# touch-board-ks-edition.net
KiCad netlist of a schematic drawn in EAGLE
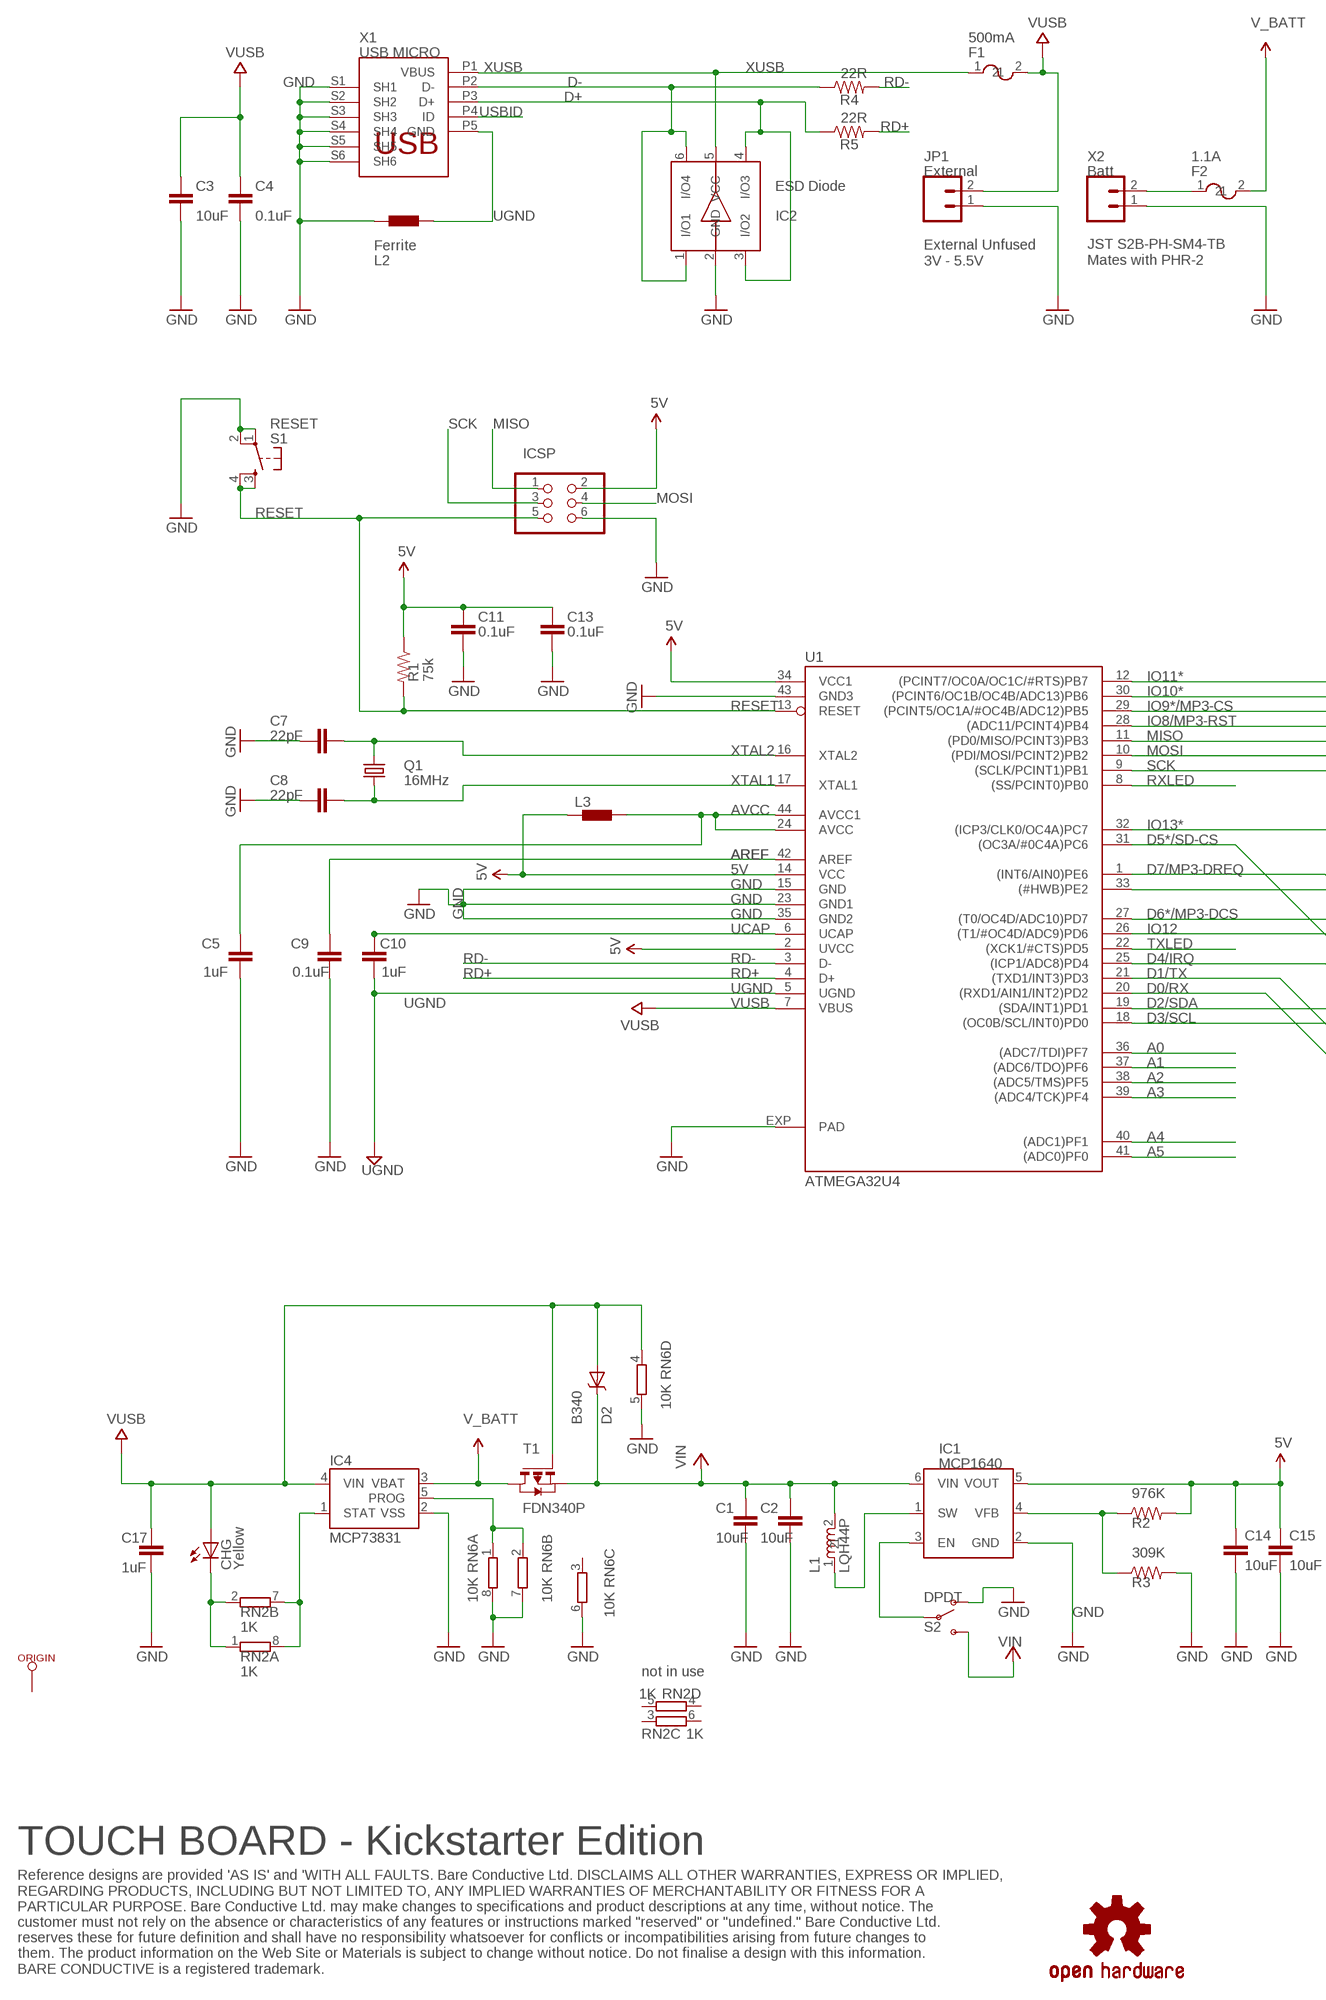
[diagram p0: schematic, sheet 1, part 1 of 2]
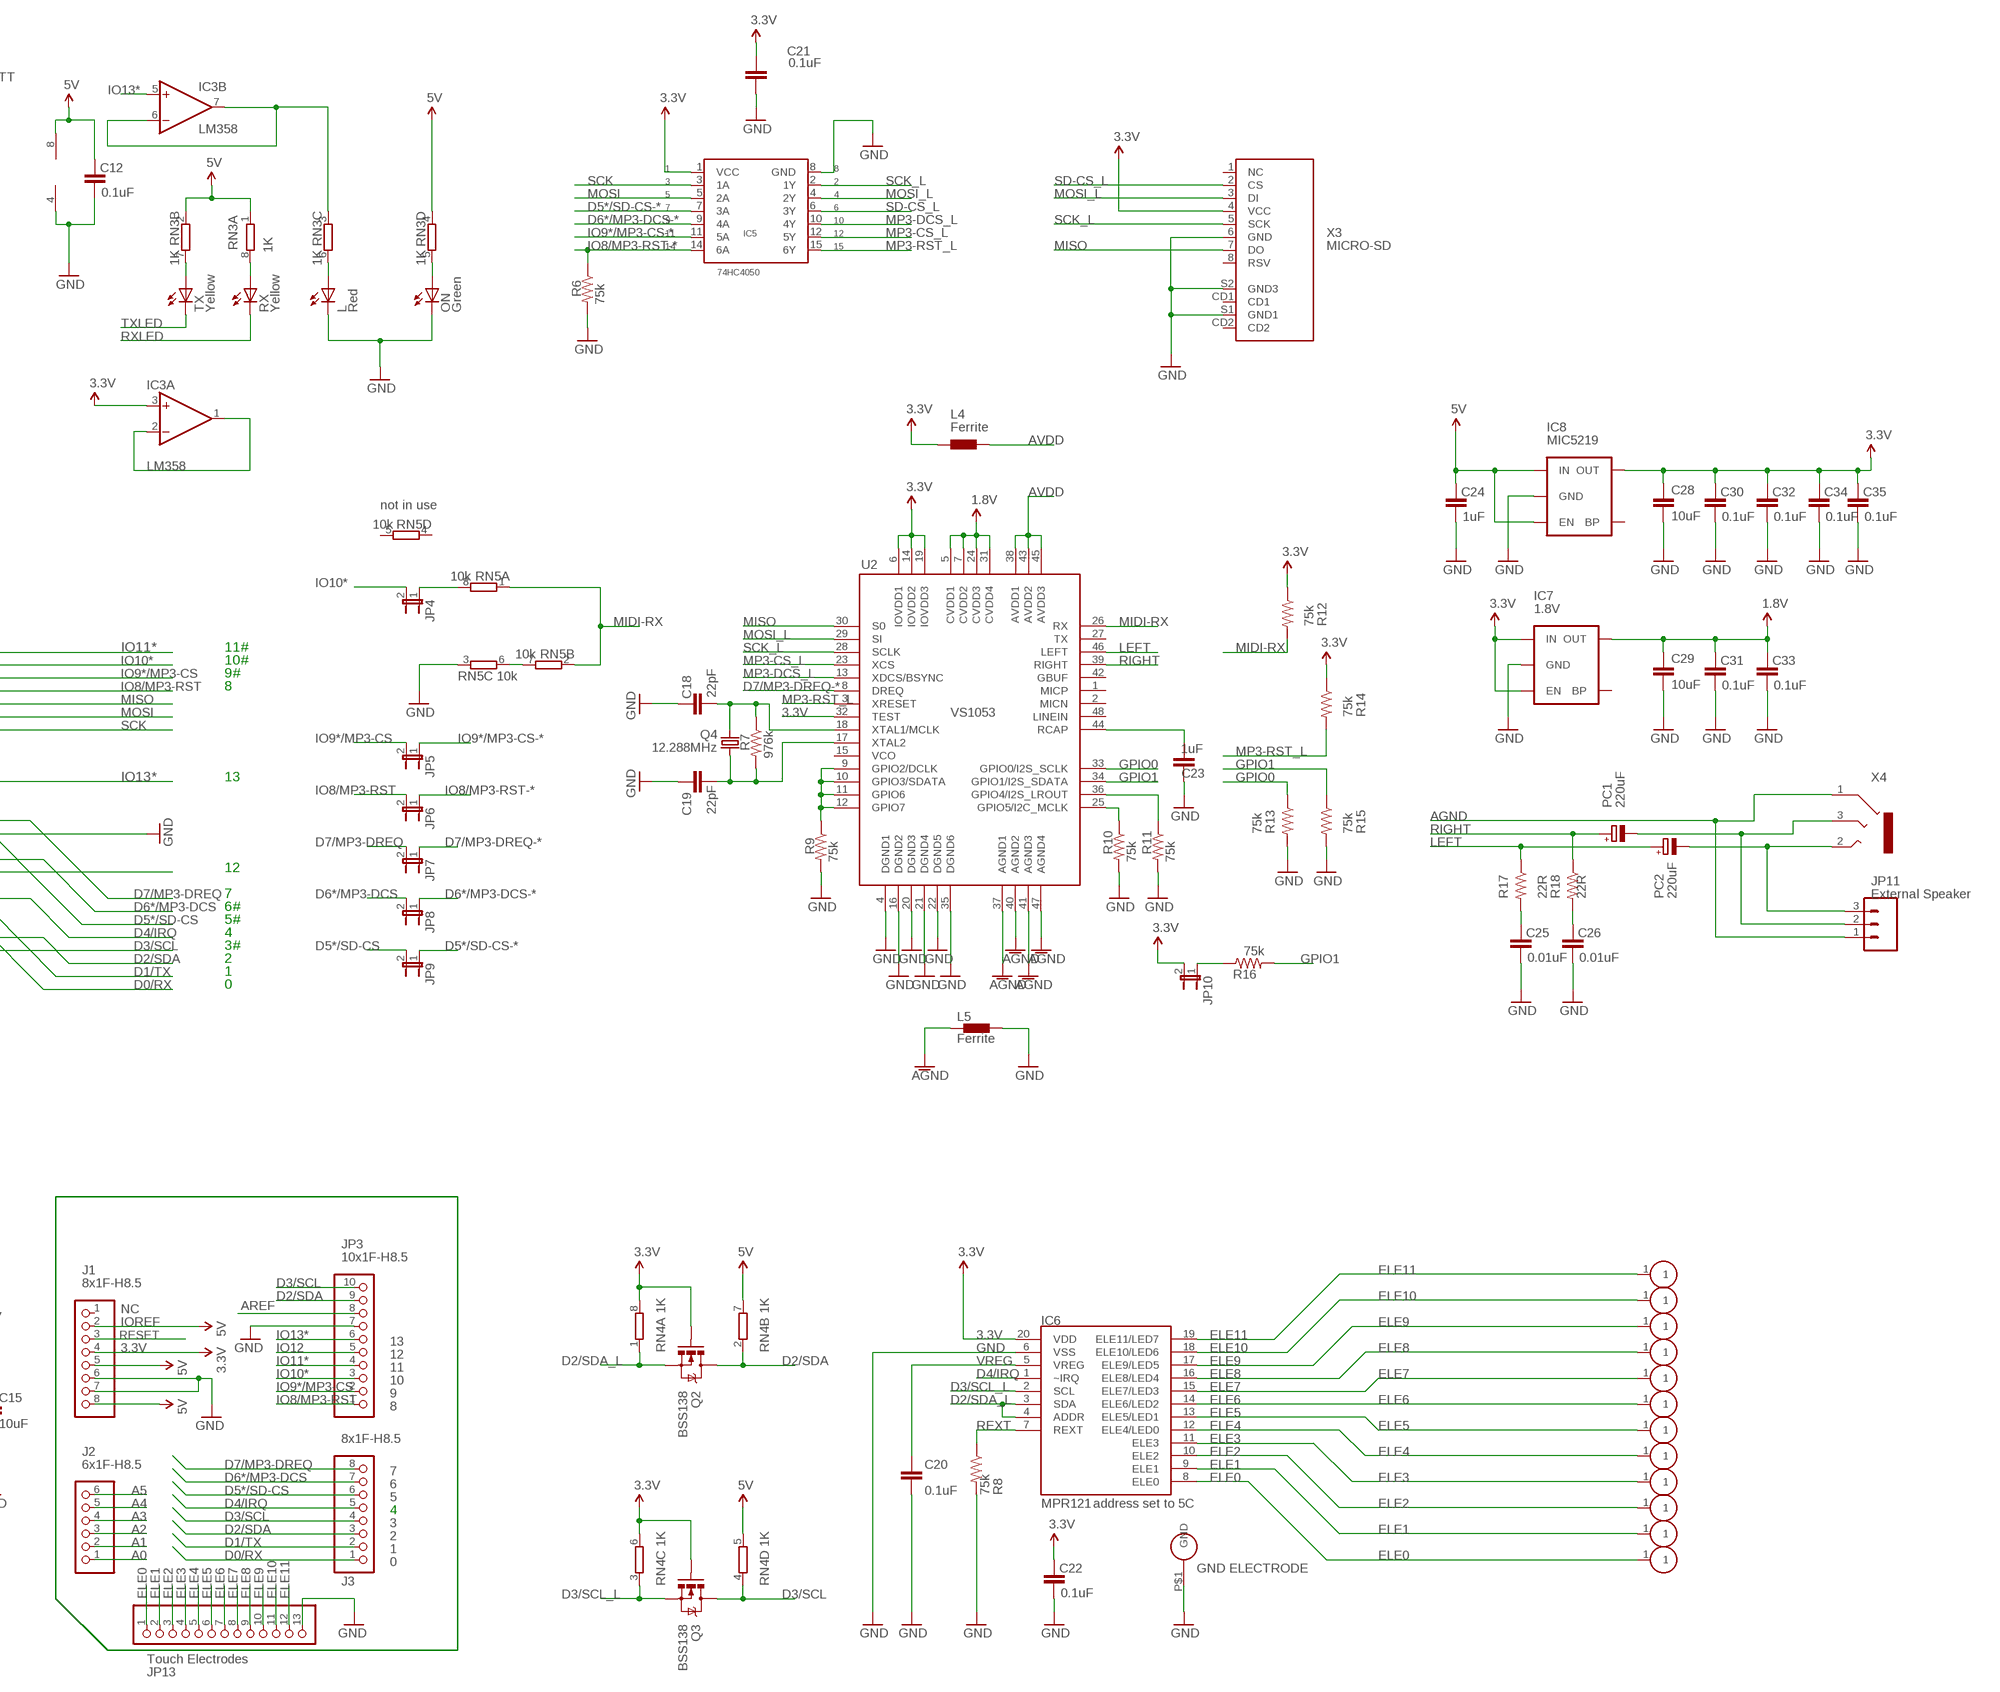
[diagram p1: schematic, sheet 1, part 2 of 2]

(export (version "E")
  (design (tool "Eeschema 10.0.6"))
  (components
    (comp (ref "C1")
      (value "10uF")
      (footprint "eagle-import:1206")
      (libsource (lib "eagle-import") (part "SparkFun-Capacitors_CAP1206"))
    )
    (comp (ref "C2")
      (value "10uF")
      (footprint "eagle-import:1206")
      (libsource (lib "eagle-import") (part "SparkFun-Capacitors_CAP1206"))
    )
    (comp (ref "C3")
      (value "10uF")
      (footprint "eagle-import:1206")
      (libsource (lib "eagle-import") (part "SparkFun-Capacitors_CAP1206"))
    )
    (comp (ref "C4")
      (value "0.1uF")
      (footprint "eagle-import:0402-CAP")
      (libsource (lib "eagle-import") (part "CAP0402-CAP"))
    )
    (comp (ref "C5")
      (value "1uF")
      (footprint "eagle-import:0402-CAP")
      (libsource (lib "eagle-import") (part "CAP0402-CAP"))
    )
    (comp (ref "C7")
      (value "22pF")
      (footprint "eagle-import:0402-CAP")
      (libsource (lib "eagle-import") (part "CAP0402-CAP"))
    )
    (comp (ref "C8")
      (value "22pF")
      (footprint "eagle-import:0402-CAP")
      (libsource (lib "eagle-import") (part "CAP0402-CAP"))
    )
    (comp (ref "C9")
      (value "0.1uF")
      (footprint "eagle-import:0402-CAP")
      (libsource (lib "eagle-import") (part "CAP0402-CAP"))
    )
    (comp (ref "C10")
      (value "1uF")
      (footprint "eagle-import:0402-CAP")
      (libsource (lib "eagle-import") (part "CAP0402-CAP"))
    )
    (comp (ref "C11")
      (value "0.1uF")
      (footprint "eagle-import:0402-CAP")
      (libsource (lib "eagle-import") (part "CAP0402-CAP"))
    )
    (comp (ref "C12")
      (value "0.1uF")
      (footprint "eagle-import:0402-CAP")
      (libsource (lib "eagle-import") (part "CAP0402-CAP"))
    )
    (comp (ref "C13")
      (value "0.1uF")
      (footprint "eagle-import:0402-CAP")
      (libsource (lib "eagle-import") (part "CAP0402-CAP"))
    )
    (comp (ref "C14")
      (value "10uF")
      (footprint "eagle-import:1206")
      (libsource (lib "eagle-import") (part "SparkFun-Capacitors_CAP1206"))
    )
    (comp (ref "C15")
      (value "10uF")
      (footprint "eagle-import:1206")
      (libsource (lib "eagle-import") (part "SparkFun-Capacitors_CAP1206"))
    )
    (comp (ref "C17")
      (value "1uF")
      (footprint "eagle-import:0402-CAP")
      (libsource (lib "eagle-import") (part "CAP0402-CAP"))
    )
    (comp (ref "C18")
      (value "22pF")
      (footprint "eagle-import:0402-CAP")
      (libsource (lib "eagle-import") (part "CAP0402-CAP"))
    )
    (comp (ref "C19")
      (value "22pF")
      (footprint "eagle-import:0402-CAP")
      (libsource (lib "eagle-import") (part "CAP0402-CAP"))
    )
    (comp (ref "C20")
      (value "0.1uF")
      (footprint "eagle-import:0402-CAP")
      (libsource (lib "eagle-import") (part "CAP0402-CAP"))
    )
    (comp (ref "C21")
      (value "0.1uF")
      (footprint "eagle-import:0402-CAP")
      (libsource (lib "eagle-import") (part "CAP0402-CAP"))
    )
    (comp (ref "C22")
      (value "0.1uF")
      (footprint "eagle-import:0402-CAP")
      (libsource (lib "eagle-import") (part "CAP0402-CAP"))
    )
    (comp (ref "C23")
      (value "1uF")
      (footprint "eagle-import:0402-CAP")
      (libsource (lib "eagle-import") (part "CAP0402-CAP"))
    )
    (comp (ref "C24")
      (value "1uF")
      (footprint "eagle-import:0402-CAP")
      (libsource (lib "eagle-import") (part "CAP0402-CAP"))
    )
    (comp (ref "C25")
      (value "0.01uF")
      (footprint "eagle-import:0402-CAP")
      (libsource (lib "eagle-import") (part "CAP0402-CAP"))
    )
    (comp (ref "C26")
      (value "0.01uF")
      (footprint "eagle-import:0402-CAP")
      (libsource (lib "eagle-import") (part "CAP0402-CAP"))
    )
    (comp (ref "C28")
      (value "10uF")
      (footprint "eagle-import:1206")
      (libsource (lib "eagle-import") (part "SparkFun-Capacitors_CAP1206"))
    )
    (comp (ref "C29")
      (value "10uF")
      (footprint "eagle-import:1206")
      (libsource (lib "eagle-import") (part "SparkFun-Capacitors_CAP1206"))
    )
    (comp (ref "C30")
      (value "0.1uF")
      (footprint "eagle-import:0402-CAP")
      (libsource (lib "eagle-import") (part "CAP0402-CAP"))
    )
    (comp (ref "C31")
      (value "0.1uF")
      (footprint "eagle-import:0402-CAP")
      (libsource (lib "eagle-import") (part "CAP0402-CAP"))
    )
    (comp (ref "C32")
      (value "0.1uF")
      (footprint "eagle-import:0402-CAP")
      (libsource (lib "eagle-import") (part "CAP0402-CAP"))
    )
    (comp (ref "C33")
      (value "0.1uF")
      (footprint "eagle-import:0402-CAP")
      (libsource (lib "eagle-import") (part "CAP0402-CAP"))
    )
    (comp (ref "C34")
      (value "0.1uF")
      (footprint "eagle-import:0402-CAP")
      (libsource (lib "eagle-import") (part "CAP0402-CAP"))
    )
    (comp (ref "C35")
      (value "0.1uF")
      (footprint "eagle-import:0402-CAP")
      (libsource (lib "eagle-import") (part "CAP0402-CAP"))
    )
    (comp (ref "CHG")
      (value "Yellow")
      (footprint "eagle-import:CHIPLED_0805")
      (libsource (lib "eagle-import") (part "LEDCHIPLED_0805"))
    )
    (comp (ref "D2")
      (value "B340")
      (footprint "eagle-import:SMA-DIODE")
      (libsource (lib "eagle-import") (part "DIODE-SCHOTTKY_"))
    )
    (comp (ref "F1")
      (value "500mA")
      (footprint "eagle-import:0805")
      (libsource (lib "eagle-import") (part "PTC"))
    )
    (comp (ref "F2")
      (value "1.1A")
      (footprint "eagle-import:0805")
      (libsource (lib "eagle-import") (part "PTC"))
    )
    (comp (ref "IC1")
      (value "MCP1640")
      (footprint "eagle-import:6-LEAD-SOT23")
      (libsource (lib "eagle-import") (part "BOOST-REG"))
    )
    (comp (ref "IC2")
      (value "ESD Diode")
      (footprint "eagle-import:SOT457")
      (libsource (lib "eagle-import") (part "PRTR5V"))
    )
    (comp (ref "IC3")
      (value "LM358")
      (footprint "eagle-import:MSOP08")
      (libsource (lib "eagle-import") (part "LMV358?MMX"))
    )
    (comp (ref "IC4")
      (value "MCP73831")
      (footprint "eagle-import:SOT23-5")
      (libsource (lib "eagle-import") (part "MCP73831"))
    )
    (comp (ref "IC5")
      (value "74HC4050")
      (footprint "eagle-import:TSSOP-16")
      (libsource (lib "eagle-import") (part "74HC4050PW"))
    )
    (comp (ref "IC6")
      (value "MPR121")
      (footprint "eagle-import:QFN-20-0.4MM")
      (libsource (lib "eagle-import") (part "MPR121QFN20"))
    )
    (comp (ref "IC7")
      (value "1.8V")
      (footprint "eagle-import:SC70")
      (libsource (lib "eagle-import") (part "V_REG_LDOSMD2"))
    )
    (comp (ref "IC8")
      (value "MIC5219")
      (footprint "eagle-import:SOT23-5")
      (libsource (lib "eagle-import") (part "V_REG_LDOSMD"))
    )
    (comp (ref "ICSP")
      (value "ICSP")
      (footprint "eagle-import:2X03")
      (libsource (lib "eagle-import") (part "PINHD-2X3"))
    )
    (comp (ref "J1")
      (value "8x1F-H8.5")
      (footprint "eagle-import:1X08")
      (libsource (lib "eagle-import") (part "PINHD-1X8"))
    )
    (comp (ref "J2")
      (value "6x1F-H8.5")
      (footprint "eagle-import:1X06")
      (libsource (lib "eagle-import") (part "PINHD-1X6"))
    )
    (comp (ref "J3")
      (value "8x1F-H8.5")
      (footprint "eagle-import:1X08")
      (libsource (lib "eagle-import") (part "PINHD-1X8"))
    )
    (comp (ref "JP1")
      (value "External")
      (footprint "eagle-import:1X02")
      (libsource (lib "eagle-import") (part "M02PTH"))
    )
    (comp (ref "JP3")
      (value "10x1F-H8.5")
      (footprint "eagle-import:1X10")
      (libsource (lib "eagle-import") (part "PINHD-1X10"))
    )
    (comp (ref "JP4")
      (value "JUMPER-2SMD-NO")
      (footprint "eagle-import:SJ_2S-NO")
      (libsource (lib "eagle-import") (part "JUMPER-2SMD-NO"))
    )
    (comp (ref "JP5")
      (value "JUMPER-2SMD-NC")
      (footprint "eagle-import:SJ_2S")
      (libsource (lib "eagle-import") (part "JUMPER-2SMD-NC"))
    )
    (comp (ref "JP6")
      (value "JUMPER-2SMD-NC")
      (footprint "eagle-import:SJ_2S")
      (libsource (lib "eagle-import") (part "JUMPER-2SMD-NC"))
    )
    (comp (ref "JP7")
      (value "JUMPER-2SMD-NC")
      (footprint "eagle-import:SJ_2S")
      (libsource (lib "eagle-import") (part "JUMPER-2SMD-NC"))
    )
    (comp (ref "JP8")
      (value "JUMPER-2SMD-NC")
      (footprint "eagle-import:SJ_2S")
      (libsource (lib "eagle-import") (part "JUMPER-2SMD-NC"))
    )
    (comp (ref "JP9")
      (value "JUMPER-2SMD-NC")
      (footprint "eagle-import:SJ_2S")
      (libsource (lib "eagle-import") (part "JUMPER-2SMD-NC"))
    )
    (comp (ref "JP10")
      (value "JUMPER-2SMD-NO")
      (footprint "eagle-import:SJ_2S-NO")
      (libsource (lib "eagle-import") (part "JUMPER-2SMD-NO"))
    )
    (comp (ref "JP11")
      (value "External Speaker")
      (footprint "eagle-import:1X03")
      (libsource (lib "eagle-import") (part "M03PTH"))
    )
    (comp (ref "JP13")
      (value "Touch Electrodes")
      (footprint "eagle-import:1X13")
      (libsource (lib "eagle-import") (part "PINHD-1X13"))
    )
    (comp (ref "L")
      (value "Red")
      (footprint "eagle-import:CHIPLED_0805")
      (libsource (lib "eagle-import") (part "LEDCHIPLED_0805"))
    )
    (comp (ref "L1")
      (value "LQH44P")
      (footprint "eagle-import:LQH44PN100MP0L")
      (libsource (lib "eagle-import") (part "LQH44P"))
    )
    (comp (ref "L2")
      (value "Ferrite")
      (footprint "eagle-import:0402")
      (libsource (lib "eagle-import") (part "BLM15HB121SN1"))
    )
    (comp (ref "L3")
      (value "BLM15HB121SN1")
      (footprint "eagle-import:0402")
      (libsource (lib "eagle-import") (part "BLM15HB121SN1"))
    )
    (comp (ref "L4")
      (value "Ferrite")
      (footprint "eagle-import:0402")
      (libsource (lib "eagle-import") (part "BLM15HB121SN1"))
    )
    (comp (ref "L5")
      (value "Ferrite")
      (footprint "eagle-import:0402")
      (libsource (lib "eagle-import") (part "BLM15HB121SN1"))
    )
    (comp (ref "ON")
      (value "Green")
      (footprint "eagle-import:CHIPLED_0805")
      (libsource (lib "eagle-import") (part "LEDCHIPLED_0805"))
    )
    (comp (ref "ORIGIN")
      (value "TP_SP")
      (footprint "eagle-import:TP-SP")
      (libsource (lib "eagle-import") (part "TP_SP"))
    )
    (comp (ref "PC1")
      (value "220uF")
      (footprint "eagle-import:PANASONIC_D")
      (libsource (lib "eagle-import") (part "CPOL-EUD"))
    )
    (comp (ref "PC2")
      (value "220uF")
      (footprint "eagle-import:PANASONIC_D")
      (libsource (lib "eagle-import") (part "CPOL-EUD"))
    )
    (comp (ref "Q1")
      (value "16MHz")
      (footprint "eagle-import:CRYSTAL-SMD-5X3")
      (libsource (lib "eagle-import") (part "CRYSTAL5X3"))
    )
    (comp (ref "Q2")
      (value "BSS138")
      (footprint "eagle-import:SOT23-3")
      (libsource (lib "eagle-import") (part "MOSFET-NCHANNELSMD"))
    )
    (comp (ref "Q3")
      (value "BSS138")
      (footprint "eagle-import:SOT23-3")
      (libsource (lib "eagle-import") (part "MOSFET-NCHANNELSMD"))
    )
    (comp (ref "Q4")
      (value "12.288MHz")
      (footprint "eagle-import:CRYSTAL-SMD-5X3")
      (libsource (lib "eagle-import") (part "CRYSTAL5X3"))
    )
    (comp (ref "R1")
      (value "75k")
      (footprint "eagle-import:0402-RES")
      (libsource (lib "eagle-import") (part "RESISTOR0402-RES"))
    )
    (comp (ref "R2")
      (value "976K")
      (footprint "eagle-import:0402-RES")
      (libsource (lib "eagle-import") (part "RESISTOR0402-RES"))
    )
    (comp (ref "R3")
      (value "309K")
      (footprint "eagle-import:0402-RES")
      (libsource (lib "eagle-import") (part "RESISTOR0402-RES"))
    )
    (comp (ref "R4")
      (value "22R")
      (footprint "eagle-import:0402-RES")
      (libsource (lib "eagle-import") (part "RESISTOR0402-RES"))
    )
    (comp (ref "R5")
      (value "22R")
      (footprint "eagle-import:0402-RES")
      (libsource (lib "eagle-import") (part "RESISTOR0402-RES"))
    )
    (comp (ref "R6")
      (value "75k")
      (footprint "eagle-import:0402-RES")
      (libsource (lib "eagle-import") (part "RESISTOR0402-RES"))
    )
    (comp (ref "R7")
      (value "976k")
      (footprint "eagle-import:0402-RES")
      (libsource (lib "eagle-import") (part "RESISTOR0402-RES"))
    )
    (comp (ref "R8")
      (value "75k")
      (footprint "eagle-import:0402-RES")
      (libsource (lib "eagle-import") (part "RESISTOR0402-RES"))
    )
    (comp (ref "R9")
      (value "75k")
      (footprint "eagle-import:0402-RES")
      (libsource (lib "eagle-import") (part "RESISTOR0402-RES"))
    )
    (comp (ref "R10")
      (value "75k")
      (footprint "eagle-import:0402-RES")
      (libsource (lib "eagle-import") (part "RESISTOR0402-RES"))
    )
    (comp (ref "R11")
      (value "75k")
      (footprint "eagle-import:0402-RES")
      (libsource (lib "eagle-import") (part "RESISTOR0402-RES"))
    )
    (comp (ref "R12")
      (value "75k")
      (footprint "eagle-import:0402-RES")
      (libsource (lib "eagle-import") (part "RESISTOR0402-RES"))
    )
    (comp (ref "R13")
      (value "75k")
      (footprint "eagle-import:0402-RES")
      (libsource (lib "eagle-import") (part "RESISTOR0402-RES"))
    )
    (comp (ref "R14")
      (value "75k")
      (footprint "eagle-import:0402-RES")
      (libsource (lib "eagle-import") (part "RESISTOR0402-RES"))
    )
    (comp (ref "R15")
      (value "75k")
      (footprint "eagle-import:0402-RES")
      (libsource (lib "eagle-import") (part "RESISTOR0402-RES"))
    )
    (comp (ref "R16")
      (value "75k")
      (footprint "eagle-import:0402-RES")
      (libsource (lib "eagle-import") (part "RESISTOR0402-RES"))
    )
    (comp (ref "R17")
      (value "22R")
      (footprint "eagle-import:0402-RES")
      (libsource (lib "eagle-import") (part "RESISTOR0402-RES"))
    )
    (comp (ref "R18")
      (value "22R")
      (footprint "eagle-import:0402-RES")
      (libsource (lib "eagle-import") (part "RESISTOR0402-RES"))
    )
    (comp (ref "RN2")
      (value "1K")
      (footprint "eagle-import:CAY16")
      (libsource (lib "eagle-import") (part "4R-NCAY16"))
    )
    (comp (ref "RN3")
      (value "1K")
      (footprint "eagle-import:CAY16")
      (libsource (lib "eagle-import") (part "4R-NCAY16"))
    )
    (comp (ref "RN4")
      (value "1K")
      (footprint "eagle-import:CAY16")
      (libsource (lib "eagle-import") (part "4R-NCAY16"))
    )
    (comp (ref "RN5")
      (value "10k")
      (footprint "eagle-import:CAY16")
      (libsource (lib "eagle-import") (part "4R-NCAY16"))
    )
    (comp (ref "RN6")
      (value "10K")
      (footprint "eagle-import:CAY16")
      (libsource (lib "eagle-import") (part "4R-NCAY16"))
    )
    (comp (ref "RX")
      (value "Yellow")
      (footprint "eagle-import:CHIPLED_0805")
      (libsource (lib "eagle-import") (part "LEDCHIPLED_0805"))
    )
    (comp (ref "S1")
      (value "RESET")
      (footprint "eagle-import:TACTILE_SWITCH_SMD@1")
      (libsource (lib "eagle-import") (part "TAC_SWITCHSND"))
    )
    (comp (ref "S2")
      (value "DPDT")
      (footprint "eagle-import:JS202011SCQN")
      (libsource (lib "eagle-import") (part "DPDT-SWITCH"))
    )
    (comp (ref "T1")
      (value "FDN340P")
      (footprint "eagle-import:SOT-23")
      (libsource (lib "eagle-import") (part "PMOSSOT23"))
    )
    (comp (ref "TX")
      (value "Yellow")
      (footprint "eagle-import:CHIPLED_0805")
      (libsource (lib "eagle-import") (part "LEDCHIPLED_0805"))
    )
    (comp (ref "U$1")
      (value "EDGE-ELEC-LEFT")
      (footprint "eagle-import:EDGE-ELEC-LEFT")
      (libsource (lib "eagle-import") (part "EDGE-ELEC-LEFT"))
    )
    (comp (ref "U$3")
      (value "EDGE-ELEC-RIGHT")
      (footprint "eagle-import:EDGE-ELEC-RIGHT")
      (libsource (lib "eagle-import") (part "EDGE-ELEC-RIGHT"))
    )
    (comp (ref "U$6")
      (value "EDGE-GND")
      (footprint "eagle-import:EDGE-GND")
      (libsource (lib "eagle-import") (part "EDGE-GND"))
    )
    (comp (ref "U$8")
      (value "OSHW-LOGO")
      (footprint "eagle-import:OSHW-LOGO")
      (libsource (lib "eagle-import") (part "OSHW-LOGO"))
    )
    (comp (ref "U$17")
      (value "EDGE-ELEC")
      (footprint "eagle-import:EDGE-ELEC")
      (libsource (lib "eagle-import") (part "EDGE-ELEC"))
    )
    (comp (ref "U$18")
      (value "EDGE-ELEC")
      (footprint "eagle-import:EDGE-ELEC")
      (libsource (lib "eagle-import") (part "EDGE-ELEC"))
    )
    (comp (ref "U$22")
      (value "EDGE-ELEC")
      (footprint "eagle-import:EDGE-ELEC")
      (libsource (lib "eagle-import") (part "EDGE-ELEC"))
    )
    (comp (ref "U$24")
      (value "EDGE-ELEC")
      (footprint "eagle-import:EDGE-ELEC")
      (libsource (lib "eagle-import") (part "EDGE-ELEC"))
    )
    (comp (ref "U$26")
      (value "EDGE-ELEC")
      (footprint "eagle-import:EDGE-ELEC")
      (libsource (lib "eagle-import") (part "EDGE-ELEC"))
    )
    (comp (ref "U$27")
      (value "EDGE-ELEC")
      (footprint "eagle-import:EDGE-ELEC")
      (libsource (lib "eagle-import") (part "EDGE-ELEC"))
    )
    (comp (ref "U$28")
      (value "EDGE-ELEC")
      (footprint "eagle-import:EDGE-ELEC")
      (libsource (lib "eagle-import") (part "EDGE-ELEC"))
    )
    (comp (ref "U$29")
      (value "EDGE-ELEC")
      (footprint "eagle-import:EDGE-ELEC")
      (libsource (lib "eagle-import") (part "EDGE-ELEC"))
    )
    (comp (ref "U$30")
      (value "EDGE-ELEC")
      (footprint "eagle-import:EDGE-ELEC")
      (libsource (lib "eagle-import") (part "EDGE-ELEC"))
    )
    (comp (ref "U$31")
      (value "EDGE-ELEC")
      (footprint "eagle-import:EDGE-ELEC")
      (libsource (lib "eagle-import") (part "EDGE-ELEC"))
    )
    (comp (ref "U1")
      (value "ATMEGA32U4")
      (footprint "eagle-import:QFN44ML7X7")
      (libsource (lib "eagle-import") (part "ATMEGA32U4-XUMU"))
    )
    (comp (ref "U2")
      (value "VS1053")
      (footprint "eagle-import:LQFP-48")
      (libsource (lib "eagle-import") (part "VS1033"))
    )
    (comp (ref "X1")
      (value "USB MICRO")
      (footprint "eagle-import:CON2_USB_MICRO_B_AT")
      (libsource (lib "eagle-import") (part "MYCON2_USB-MINI-B"))
    )
    (comp (ref "X2")
      (value "Batt")
      (footprint "eagle-import:JST-2-SMD")
      (libsource (lib "eagle-import") (part "M02-JST-2MM-SMT"))
    )
    (comp (ref "X3")
      (value "MICRO-SD")
      (footprint "eagle-import:MSDC-PP-02")
      (libsource (lib "eagle-import") (part "TOBY-SD"))
    )
    (comp (ref "X4")
      (value "SJ-3523")
      (footprint "eagle-import:3POLE-JACK")
      (libsource (lib "eagle-import") (part "SJ-3523"))
    )
  )
  (nets
    (net (code "1") (name "/A0") (class "Default")
      (node (ref "J2") (pin "1") (pinfunction "1_1") (pintype "passive"))
      (node (ref "U1") (pin "36") (pinfunction "(ADC7/TDI)PF7_36") (pintype "bidirectional"))
    )
    (net (code "2") (name "/A1") (class "Default")
      (node (ref "J2") (pin "2") (pinfunction "2_2") (pintype "passive"))
      (node (ref "U1") (pin "37") (pinfunction "(ADC6/TDO)PF6_37") (pintype "bidirectional"))
    )
    (net (code "3") (name "/A2") (class "Default")
      (node (ref "J2") (pin "3") (pinfunction "3_3") (pintype "passive"))
      (node (ref "U1") (pin "38") (pinfunction "(ADC5/TMS)PF5_38") (pintype "bidirectional"))
    )
    (net (code "4") (name "/A3") (class "Default")
      (node (ref "J2") (pin "4") (pinfunction "4_4") (pintype "passive"))
      (node (ref "U1") (pin "39") (pinfunction "(ADC4/TCK)PF4_39") (pintype "bidirectional"))
    )
    (net (code "5") (name "/A4") (class "Default")
      (node (ref "J2") (pin "5") (pinfunction "5_5") (pintype "passive"))
      (node (ref "U1") (pin "40") (pinfunction "(ADC1)PF1_40") (pintype "bidirectional"))
    )
    (net (code "6") (name "/A5") (class "Default")
      (node (ref "J2") (pin "6") (pinfunction "6_6") (pintype "passive"))
      (node (ref "U1") (pin "41") (pinfunction "(ADC0)PF0_41") (pintype "bidirectional"))
    )
    (net (code "7") (name "/AREF") (class "Default")
      (node (ref "C9") (pin "2") (pinfunction "2_2") (pintype "passive"))
      (node (ref "JP3") (pin "8") (pinfunction "8_8") (pintype "passive"))
      (node (ref "U1") (pin "42") (pinfunction "AREF_42") (pintype "power_in"))
    )
    (net (code "8") (name "/AVCC") (class "Default")
      (node (ref "C5") (pin "2") (pinfunction "2_2") (pintype "passive"))
      (node (ref "L3") (pin "2") (pinfunction "2_2") (pintype "passive"))
      (node (ref "U1") (pin "24") (pinfunction "AVCC_24") (pintype "power_in"))
      (node (ref "U1") (pin "44") (pinfunction "AVCC1_44") (pintype "power_in"))
    )
    (net (code "9") (name "/AVDD") (class "Default")
      (node (ref "L4") (pin "2") (pinfunction "2_2") (pintype "passive"))
      (node (ref "U2") (pin "38") (pinfunction "AVDD1_38") (pintype "bidirectional"))
      (node (ref "U2") (pin "43") (pinfunction "AVDD2_43") (pintype "bidirectional"))
      (node (ref "U2") (pin "45") (pinfunction "AVDD3_45") (pintype "bidirectional"))
    )
    (net (code "10") (name "/D+") (class "Default")
      (node (ref "IC2") (pin "3") (pinfunction "I/O2_3") (pintype "bidirectional"))
      (node (ref "IC2") (pin "4") (pinfunction "I/O3_4") (pintype "bidirectional"))
      (node (ref "R5") (pin "1") (pinfunction "1_1") (pintype "passive"))
      (node (ref "X1") (pin "P3") (pinfunction "D+_P3") (pintype "bidirectional"))
    )
    (net (code "11") (name "/D-") (class "Default")
      (node (ref "IC2") (pin "1") (pinfunction "I/O1_1") (pintype "bidirectional"))
      (node (ref "IC2") (pin "6") (pinfunction "I/O4_6") (pintype "bidirectional"))
      (node (ref "R4") (pin "1") (pinfunction "1_1") (pintype "passive"))
      (node (ref "X1") (pin "P2") (pinfunction "D-_P2") (pintype "bidirectional"))
    )
    (net (code "12") (name "/D0{slash}RX") (class "Default")
      (node (ref "J3") (pin "1") (pinfunction "1_1") (pintype "passive"))
      (node (ref "U1") (pin "20") (pinfunction "(RXD1/AIN1/INT2)PD2_20") (pintype "bidirectional"))
    )
    (net (code "13") (name "/D1{slash}TX") (class "Default")
      (node (ref "J3") (pin "2") (pinfunction "2_2") (pintype "passive"))
      (node (ref "U1") (pin "21") (pinfunction "(TXD1/INT3)PD3_21") (pintype "bidirectional"))
    )
    (net (code "14") (name "/D2{slash}SDA") (class "Default")
      (node (ref "J3") (pin "3") (pinfunction "3_3") (pintype "passive"))
      (node (ref "JP3") (pin "9") (pinfunction "9_9") (pintype "passive"))
      (node (ref "Q2") (pin "3") (pinfunction "D_3") (pintype "passive"))
      (node (ref "RN4") (pin "2") (pinfunction "1_2") (pintype "passive"))
      (node (ref "U1") (pin "19") (pinfunction "(SDA/INT1)PD1_19") (pintype "bidirectional"))
    )
    (net (code "15") (name "/D2{slash}SDA_L") (class "Default")
      (node (ref "IC6") (pin "3") (pinfunction "SDA_3") (pintype "bidirectional"))
      (node (ref "IC6") (pin "4") (pinfunction "ADDR_4") (pintype "bidirectional"))
      (node (ref "Q2") (pin "2") (pinfunction "S_2") (pintype "passive"))
      (node (ref "RN4") (pin "1") (pinfunction "1_1") (pintype "passive"))
    )
    (net (code "16") (name "/D3{slash}SCL") (class "Default")
      (node (ref "J3") (pin "4") (pinfunction "4_4") (pintype "passive"))
      (node (ref "JP3") (pin "10") (pinfunction "10_10") (pintype "passive"))
      (node (ref "Q3") (pin "3") (pinfunction "D_3") (pintype "passive"))
      (node (ref "RN4") (pin "4") (pinfunction "1_4") (pintype "passive"))
      (node (ref "U1") (pin "18") (pinfunction "(OC0B/SCL/INT0)PD0_18") (pintype "bidirectional"))
    )
    (net (code "17") (name "/D3{slash}SCL_L") (class "Default")
      (node (ref "IC6") (pin "2") (pinfunction "SCL_2") (pintype "bidirectional"))
      (node (ref "Q3") (pin "2") (pinfunction "S_2") (pintype "passive"))
      (node (ref "RN4") (pin "3") (pinfunction "1_3") (pintype "passive"))
    )
    (net (code "18") (name "/D4{slash}IRQ") (class "Default")
      (node (ref "IC6") (pin "1") (pinfunction "~{IRQ}_1") (pintype "bidirectional"))
      (node (ref "J3") (pin "5") (pinfunction "5_5") (pintype "passive"))
      (node (ref "U1") (pin "25") (pinfunction "(ICP1/ADC8)PD4_25") (pintype "bidirectional"))
    )
    (net (code "19") (name "/D5*{slash}SD-CS") (class "Default")
      (node (ref "J3") (pin "6") (pinfunction "6_6") (pintype "passive"))
      (node (ref "JP9") (pin "2") (pinfunction "2_2") (pintype "passive"))
      (node (ref "U1") (pin "31") (pinfunction "(OC3A/#0C4A)PC6_31") (pintype "bidirectional"))
    )
    (net (code "20") (name "/D5*{slash}SD-CS-*") (class "Default")
      (node (ref "IC5") (pin "7") (pinfunction "3A_7") (pintype "bidirectional"))
      (node (ref "JP9") (pin "1") (pinfunction "1_1") (pintype "passive"))
    )
    (net (code "21") (name "/D6*{slash}MP3-DCS") (class "Default")
      (node (ref "J3") (pin "7") (pinfunction "7_7") (pintype "passive"))
      (node (ref "JP8") (pin "2") (pinfunction "2_2") (pintype "passive"))
      (node (ref "U1") (pin "27") (pinfunction "(T0/OC4D/ADC10)PD7_27") (pintype "bidirectional"))
    )
    (net (code "22") (name "/D6*{slash}MP3-DCS-*") (class "Default")
      (node (ref "IC5") (pin "9") (pinfunction "4A_9") (pintype "bidirectional"))
      (node (ref "JP8") (pin "1") (pinfunction "1_1") (pintype "passive"))
    )
    (net (code "23") (name "/D7{slash}MP3-DREQ") (class "Default")
      (node (ref "J3") (pin "8") (pinfunction "8_8") (pintype "passive"))
      (node (ref "JP7") (pin "2") (pinfunction "2_2") (pintype "passive"))
      (node (ref "U1") (pin "1") (pinfunction "(INT6/AIN0)PE6_1") (pintype "bidirectional"))
    )
    (net (code "24") (name "/D7{slash}MP3-DREQ-*") (class "Default")
      (node (ref "JP7") (pin "1") (pinfunction "1_1") (pintype "passive"))
      (node (ref "U2") (pin "8") (pinfunction "DREQ_8") (pintype "bidirectional"))
    )
    (net (code "25") (name "/ELE0") (class "Default")
      (node (ref "IC6") (pin "8") (pinfunction "ELE0_8") (pintype "bidirectional"))
      (node (ref "JP13") (pin "1") (pinfunction "1_1") (pintype "passive"))
      (node (ref "U$1") (pin "1") (pinfunction "1_1") (pintype "bidirectional"))
    )
    (net (code "26") (name "/ELE1") (class "Default")
      (node (ref "IC6") (pin "9") (pinfunction "ELE1_9") (pintype "bidirectional"))
      (node (ref "JP13") (pin "2") (pinfunction "2_2") (pintype "passive"))
      (node (ref "U$31") (pin "1") (pinfunction "1_1") (pintype "bidirectional"))
    )
    (net (code "27") (name "/ELE2") (class "Default")
      (node (ref "IC6") (pin "10") (pinfunction "ELE2_10") (pintype "bidirectional"))
      (node (ref "JP13") (pin "3") (pinfunction "3_3") (pintype "passive"))
      (node (ref "U$30") (pin "1") (pinfunction "1_1") (pintype "bidirectional"))
    )
    (net (code "28") (name "/ELE3") (class "Default")
      (node (ref "IC6") (pin "11") (pinfunction "ELE3_11") (pintype "bidirectional"))
      (node (ref "JP13") (pin "4") (pinfunction "4_4") (pintype "passive"))
      (node (ref "U$29") (pin "1") (pinfunction "1_1") (pintype "bidirectional"))
    )
    (net (code "29") (name "/ELE4") (class "Default")
      (node (ref "IC6") (pin "12") (pinfunction "ELE4/LED0_12") (pintype "bidirectional"))
      (node (ref "JP13") (pin "5") (pinfunction "5_5") (pintype "passive"))
      (node (ref "U$28") (pin "1") (pinfunction "1_1") (pintype "bidirectional"))
    )
    (net (code "30") (name "/ELE5") (class "Default")
      (node (ref "IC6") (pin "13") (pinfunction "ELE5/LED1_13") (pintype "bidirectional"))
      (node (ref "JP13") (pin "6") (pinfunction "6_6") (pintype "passive"))
      (node (ref "U$27") (pin "1") (pinfunction "1_1") (pintype "bidirectional"))
    )
    (net (code "31") (name "/ELE6") (class "Default")
      (node (ref "IC6") (pin "14") (pinfunction "ELE6/LED2_14") (pintype "bidirectional"))
      (node (ref "JP13") (pin "7") (pinfunction "7_7") (pintype "passive"))
      (node (ref "U$26") (pin "1") (pinfunction "1_1") (pintype "bidirectional"))
    )
    (net (code "32") (name "/ELE7") (class "Default")
      (node (ref "IC6") (pin "15") (pinfunction "ELE7/LED3_15") (pintype "bidirectional"))
      (node (ref "JP13") (pin "8") (pinfunction "8_8") (pintype "passive"))
      (node (ref "U$24") (pin "1") (pinfunction "1_1") (pintype "bidirectional"))
    )
    (net (code "33") (name "/ELE8") (class "Default")
      (node (ref "IC6") (pin "16") (pinfunction "ELE8/LED4_16") (pintype "bidirectional"))
      (node (ref "JP13") (pin "9") (pinfunction "9_9") (pintype "passive"))
      (node (ref "U$22") (pin "1") (pinfunction "1_1") (pintype "bidirectional"))
    )
    (net (code "34") (name "/ELE9") (class "Default")
      (node (ref "IC6") (pin "17") (pinfunction "ELE9/LED5_17") (pintype "bidirectional"))
      (node (ref "JP13") (pin "10") (pinfunction "10_10") (pintype "passive"))
      (node (ref "U$18") (pin "1") (pinfunction "1_1") (pintype "bidirectional"))
    )
    (net (code "35") (name "/ELE10") (class "Default")
      (node (ref "IC6") (pin "18") (pinfunction "ELE10/LED6_18") (pintype "bidirectional"))
      (node (ref "JP13") (pin "11") (pinfunction "11_11") (pintype "passive"))
      (node (ref "U$17") (pin "1") (pinfunction "1_1") (pintype "bidirectional"))
    )
    (net (code "36") (name "/ELE11") (class "Default")
      (node (ref "IC6") (pin "19") (pinfunction "ELE11/LED7_19") (pintype "bidirectional"))
      (node (ref "JP13") (pin "12") (pinfunction "12_12") (pintype "passive"))
      (node (ref "U$3") (pin "1") (pinfunction "1_1") (pintype "bidirectional"))
    )
    (net (code "37") (name "/GPIO0") (class "Default")
      (node (ref "R13") (pin "1") (pinfunction "1_1") (pintype "passive"))
      (node (ref "U2") (pin "33") (pinfunction "GPIO0/I2S_SCLK_33") (pintype "bidirectional"))
    )
    (net (code "38") (name "/GPIO1") (class "Default")
      (node (ref "R15") (pin "1") (pinfunction "1_1") (pintype "passive"))
      (node (ref "R16") (pin "2") (pinfunction "2_2") (pintype "passive"))
      (node (ref "U2") (pin "34") (pinfunction "GPIO1/I2S_SDATA_34") (pintype "bidirectional"))
    )
    (net (code "39") (name "/IO8{slash}MP3-RST") (class "Default")
      (node (ref "JP3") (pin "1") (pinfunction "1_1") (pintype "passive"))
      (node (ref "JP6") (pin "2") (pinfunction "2_2") (pintype "passive"))
      (node (ref "U1") (pin "28") (pinfunction "(ADC11/PCINT4)PB4_28") (pintype "bidirectional"))
    )
    (net (code "40") (name "/IO8{slash}MP3-RST-*") (class "Default")
      (node (ref "IC5") (pin "14") (pinfunction "6A_14") (pintype "bidirectional"))
      (node (ref "JP6") (pin "1") (pinfunction "1_1") (pintype "passive"))
      (node (ref "R6") (pin "1") (pinfunction "1_1") (pintype "passive"))
    )
    (net (code "41") (name "/IO9*{slash}MP3-CS") (class "Default")
      (node (ref "JP3") (pin "2") (pinfunction "2_2") (pintype "passive"))
      (node (ref "JP5") (pin "2") (pinfunction "2_2") (pintype "passive"))
      (node (ref "U1") (pin "29") (pinfunction "(PCINT5/OC1A/#OC4B/ADC12)PB5_29") (pintype "bidirectional"))
    )
    (net (code "42") (name "/IO9*{slash}MP3-CS-*") (class "Default")
      (node (ref "IC5") (pin "11") (pinfunction "5A_11") (pintype "bidirectional"))
      (node (ref "JP5") (pin "1") (pinfunction "1_1") (pintype "passive"))
    )
    (net (code "43") (name "/IO10*") (class "Default")
      (node (ref "JP3") (pin "3") (pinfunction "3_3") (pintype "passive"))
      (node (ref "JP4") (pin "2") (pinfunction "2_2") (pintype "passive"))
      (node (ref "U1") (pin "30") (pinfunction "(PCINT6/OC1B/OC4B/ADC13)PB6_30") (pintype "bidirectional"))
    )
    (net (code "44") (name "/IO11*") (class "Default")
      (node (ref "JP3") (pin "4") (pinfunction "4_4") (pintype "passive"))
      (node (ref "U1") (pin "12") (pinfunction "(PCINT7/OC0A/OC1C/#RTS)PB7_12") (pintype "bidirectional"))
    )
    (net (code "45") (name "/IO12") (class "Default")
      (node (ref "JP3") (pin "5") (pinfunction "5_5") (pintype "passive"))
      (node (ref "U1") (pin "26") (pinfunction "(T1/#OC4D/ADC9)PD6_26") (pintype "bidirectional"))
    )
    (net (code "46") (name "/IO13*") (class "Default")
      (node (ref "IC3") (pin "5") (pinfunction "+IN_5") (pintype "input"))
      (node (ref "JP3") (pin "6") (pinfunction "6_6") (pintype "passive"))
      (node (ref "U1") (pin "32") (pinfunction "(ICP3/CLK0/OC4A)PC7_32") (pintype "bidirectional"))
    )
    (net (code "47") (name "/LEFT") (class "Default")
      (node (ref "PC2") (pin "+") (pinfunction "+_+") (pintype "passive"))
      (node (ref "R17") (pin "1") (pinfunction "1_1") (pintype "passive"))
      (node (ref "U2") (pin "46") (pinfunction "LEFT_46") (pintype "bidirectional"))
    )
    (net (code "48") (name "/MIDI-RX") (class "Default")
      (node (ref "R12") (pin "2") (pinfunction "2_2") (pintype "passive"))
      (node (ref "RN5") (pin "1") (pinfunction "1_1") (pintype "passive"))
      (node (ref "RN5") (pin "2") (pinfunction "1_2") (pintype "passive"))
      (node (ref "U2") (pin "26") (pinfunction "RX_26") (pintype "bidirectional"))
    )
    (net (code "49") (name "/MISO") (class "Default")
      (node (ref "ICSP") (pin "1") (pinfunction "1_1") (pintype "passive"))
      (node (ref "U1") (pin "11") (pinfunction "(PD0/MISO/PCINT3)PB3_11") (pintype "bidirectional"))
      (node (ref "U2") (pin "30") (pinfunction "S0_30") (pintype "bidirectional"))
      (node (ref "X3") (pin "7") (pinfunction "DO_7") (pintype "bidirectional"))
    )
    (net (code "50") (name "/MOSI") (class "Default")
      (node (ref "IC5") (pin "5") (pinfunction "2A_5") (pintype "bidirectional"))
      (node (ref "ICSP") (pin "4") (pinfunction "4_4") (pintype "passive"))
      (node (ref "U1") (pin "10") (pinfunction "(PDI/MOSI/PCINT2)PB2_10") (pintype "bidirectional"))
    )
    (net (code "51") (name "/MOSI_L") (class "Default")
      (node (ref "IC5") (pin "4") (pinfunction "2Y_4") (pintype "bidirectional"))
      (node (ref "U2") (pin "29") (pinfunction "SI_29") (pintype "bidirectional"))
      (node (ref "X3") (pin "3") (pinfunction "DI_3") (pintype "bidirectional"))
    )
    (net (code "52") (name "/MP3-CS_L") (class "Default")
      (node (ref "IC5") (pin "12") (pinfunction "5Y_12") (pintype "bidirectional"))
      (node (ref "U2") (pin "23") (pinfunction "XCS_23") (pintype "bidirectional"))
    )
    (net (code "53") (name "/MP3-DCS_L") (class "Default")
      (node (ref "IC5") (pin "10") (pinfunction "4Y_10") (pintype "bidirectional"))
      (node (ref "U2") (pin "13") (pinfunction "XDCS/BSYNC_13") (pintype "bidirectional"))
    )
    (net (code "54") (name "/MP3-RST_L") (class "Default")
      (node (ref "IC5") (pin "15") (pinfunction "6Y_15") (pintype "bidirectional"))
      (node (ref "R14") (pin "2") (pinfunction "2_2") (pintype "passive"))
      (node (ref "U2") (pin "3") (pinfunction "XRESET_3") (pintype "bidirectional"))
    )
    (net (code "55") (name "/RD+") (class "Default")
      (node (ref "R5") (pin "2") (pinfunction "2_2") (pintype "passive"))
      (node (ref "U1") (pin "4") (pinfunction "D+_4") (pintype "bidirectional"))
    )
    (net (code "56") (name "/RD-") (class "Default")
      (node (ref "R4") (pin "2") (pinfunction "2_2") (pintype "passive"))
      (node (ref "U1") (pin "3") (pinfunction "D-_3") (pintype "bidirectional"))
    )
    (net (code "57") (name "/RESET") (class "Default")
      (node (ref "ICSP") (pin "5") (pinfunction "5_5") (pintype "passive"))
      (node (ref "J1") (pin "3") (pinfunction "3_3") (pintype "passive"))
      (node (ref "R1") (pin "2") (pinfunction "2_2") (pintype "passive"))
      (node (ref "S1") (pin "3") (pinfunction "3_3") (pintype "passive"))
      (node (ref "S1") (pin "4") (pinfunction "4_4") (pintype "passive"))
      (node (ref "U1") (pin "13") (pinfunction "RESET_13") (pintype "input"))
    )
    (net (code "58") (name "/REXT") (class "Default")
      (node (ref "IC6") (pin "7") (pinfunction "REXT_7") (pintype "bidirectional"))
      (node (ref "R8") (pin "1") (pinfunction "1_1") (pintype "passive"))
    )
    (net (code "59") (name "/RIGHT") (class "Default")
      (node (ref "PC1") (pin "+") (pinfunction "+_+") (pintype "passive"))
      (node (ref "R18") (pin "1") (pinfunction "1_1") (pintype "passive"))
      (node (ref "U2") (pin "39") (pinfunction "RIGHT_39") (pintype "bidirectional"))
    )
    (net (code "60") (name "/RXLED") (class "Default")
      (node (ref "RX") (pin "C") (pinfunction "C_C") (pintype "passive"))
      (node (ref "U1") (pin "8") (pinfunction "(SS/PCINT0)PB0_8") (pintype "bidirectional"))
    )
    (net (code "61") (name "/SCK") (class "Default")
      (node (ref "IC5") (pin "3") (pinfunction "1A_3") (pintype "bidirectional"))
      (node (ref "ICSP") (pin "3") (pinfunction "3_3") (pintype "passive"))
      (node (ref "U1") (pin "9") (pinfunction "(SCLK/PCINT1)PB1_9") (pintype "bidirectional"))
    )
    (net (code "62") (name "/SCK_L") (class "Default")
      (node (ref "IC5") (pin "2") (pinfunction "1Y_2") (pintype "bidirectional"))
      (node (ref "U2") (pin "28") (pinfunction "SCLK_28") (pintype "bidirectional"))
      (node (ref "X3") (pin "5") (pinfunction "SCK_5") (pintype "bidirectional"))
    )
    (net (code "63") (name "/SD-CS_L") (class "Default")
      (node (ref "IC5") (pin "6") (pinfunction "3Y_6") (pintype "bidirectional"))
      (node (ref "X3") (pin "2") (pinfunction "CS_2") (pintype "bidirectional"))
    )
    (net (code "64") (name "/TXLED") (class "Default")
      (node (ref "TX") (pin "C") (pinfunction "C_C") (pintype "passive"))
      (node (ref "U1") (pin "22") (pinfunction "(XCK1/#CTS)PD5_22") (pintype "bidirectional"))
    )
    (net (code "65") (name "/UCAP") (class "Default")
      (node (ref "C10") (pin "2") (pinfunction "2_2") (pintype "passive"))
      (node (ref "U1") (pin "6") (pinfunction "UCAP_6") (pintype "passive"))
    )
    (net (code "66") (name "/USBID") (class "Default")
      (node (ref "X1") (pin "P4") (pinfunction "ID_P4") (pintype "bidirectional"))
    )
    (net (code "67") (name "/VREG") (class "Default")
      (node (ref "C20") (pin "2") (pinfunction "2_2") (pintype "passive"))
      (node (ref "IC6") (pin "5") (pinfunction "VREG_5") (pintype "bidirectional"))
    )
    (net (code "68") (name "/XTAL1") (class "Default")
      (node (ref "C8") (pin "1") (pinfunction "1_1") (pintype "passive"))
      (node (ref "Q1") (pin "1") (pinfunction "1_1") (pintype "passive"))
      (node (ref "U1") (pin "17") (pinfunction "XTAL1_17") (pintype "bidirectional"))
    )
    (net (code "69") (name "/XTAL2") (class "Default")
      (node (ref "C7") (pin "1") (pinfunction "1_1") (pintype "passive"))
      (node (ref "Q1") (pin "3") (pinfunction "2_3") (pintype "passive"))
      (node (ref "U1") (pin "16") (pinfunction "XTAL2_16") (pintype "bidirectional"))
    )
    (net (code "70") (name "/XUSB") (class "Default")
      (node (ref "F1") (pin "1") (pinfunction "1_1") (pintype "bidirectional"))
      (node (ref "IC2") (pin "5") (pinfunction "VCC_5") (pintype "bidirectional"))
      (node (ref "X1") (pin "P1") (pinfunction "VBUS_P1") (pintype "power_in"))
    )
    (net (code "71") (name "1.8V") (class "Default")
      (node (ref "C29") (pin "1") (pinfunction "1_1") (pintype "passive"))
      (node (ref "C31") (pin "2") (pinfunction "2_2") (pintype "passive"))
      (node (ref "C33") (pin "2") (pinfunction "2_2") (pintype "passive"))
      (node (ref "IC7") (pin "5") (pinfunction "OUT_5") (pintype "passive"))
      (node (ref "U2") (pin "24") (pinfunction "CVDD3_24") (pintype "bidirectional"))
      (node (ref "U2") (pin "31") (pinfunction "CVDD4_31") (pintype "bidirectional"))
      (node (ref "U2") (pin "5") (pinfunction "CVDD1_5") (pintype "bidirectional"))
      (node (ref "U2") (pin "7") (pinfunction "CVDD2_7") (pintype "bidirectional"))
    )
    (net (code "72") (name "3.3V") (class "Default")
      (node (ref "C21") (pin "2") (pinfunction "2_2") (pintype "passive"))
      (node (ref "C22") (pin "2") (pinfunction "2_2") (pintype "passive"))
      (node (ref "C28") (pin "1") (pinfunction "1_1") (pintype "passive"))
      (node (ref "C30") (pin "2") (pinfunction "2_2") (pintype "passive"))
      (node (ref "C32") (pin "2") (pinfunction "2_2") (pintype "passive"))
      (node (ref "C34") (pin "2") (pinfunction "2_2") (pintype "passive"))
      (node (ref "C35") (pin "2") (pinfunction "2_2") (pintype "passive"))
      (node (ref "IC3") (pin "3") (pinfunction "+IN_3") (pintype "input"))
      (node (ref "IC5") (pin "1") (pinfunction "VCC_1") (pintype "bidirectional"))
      (node (ref "IC6") (pin "20") (pinfunction "VDD_20") (pintype "bidirectional"))
      (node (ref "IC7") (pin "1") (pinfunction "IN_1") (pintype "input"))
      (node (ref "IC7") (pin "3") (pinfunction "EN_3") (pintype "input"))
      (node (ref "IC8") (pin "5") (pinfunction "OUT_5") (pintype "passive"))
      (node (ref "J1") (pin "4") (pinfunction "4_4") (pintype "passive"))
      (node (ref "JP10") (pin "2") (pinfunction "2_2") (pintype "passive"))
      (node (ref "L4") (pin "1") (pinfunction "1_1") (pintype "passive"))
      (node (ref "Q2") (pin "1") (pinfunction "G_1") (pintype "passive"))
      (node (ref "Q3") (pin "1") (pinfunction "G_1") (pintype "passive"))
      (node (ref "R12") (pin "1") (pinfunction "1_1") (pintype "passive"))
      (node (ref "R14") (pin "1") (pinfunction "1_1") (pintype "passive"))
      (node (ref "RN4") (pin "6") (pinfunction "2_6") (pintype "passive"))
      (node (ref "RN4") (pin "8") (pinfunction "2_8") (pintype "passive"))
      (node (ref "U2") (pin "14") (pinfunction "IOVDD2_14") (pintype "bidirectional"))
      (node (ref "U2") (pin "19") (pinfunction "IOVDD3_19") (pintype "bidirectional"))
      (node (ref "U2") (pin "32") (pinfunction "TEST_32") (pintype "bidirectional"))
      (node (ref "U2") (pin "6") (pinfunction "IOVDD1_6") (pintype "bidirectional"))
      (node (ref "X3") (pin "4") (pinfunction "VCC_4") (pintype "bidirectional"))
    )
    (net (code "73") (name "5V") (class "Default")
      (node (ref "C11") (pin "2") (pinfunction "2_2") (pintype "passive"))
      (node (ref "C12") (pin "2") (pinfunction "2_2") (pintype "passive"))
      (node (ref "C13") (pin "2") (pinfunction "2_2") (pintype "passive"))
      (node (ref "C14") (pin "1") (pinfunction "1_1") (pintype "passive"))
      (node (ref "C15") (pin "1") (pinfunction "1_1") (pintype "passive"))
      (node (ref "C24") (pin "2") (pinfunction "2_2") (pintype "passive"))
      (node (ref "IC1") (pin "5") (pinfunction "VOUT_5") (pintype "bidirectional"))
      (node (ref "IC3") (pin "8") (pinfunction "V+_8") (pintype "power_in"))
      (node (ref "IC8") (pin "1") (pinfunction "IN_1") (pintype "input"))
      (node (ref "IC8") (pin "3") (pinfunction "EN_3") (pintype "input"))
      (node (ref "ICSP") (pin "2") (pinfunction "2_2") (pintype "passive"))
      (node (ref "J1") (pin "2") (pinfunction "2_2") (pintype "passive"))
      (node (ref "J1") (pin "5") (pinfunction "5_5") (pintype "passive"))
      (node (ref "J1") (pin "8") (pinfunction "8_8") (pintype "passive"))
      (node (ref "L3") (pin "1") (pinfunction "1_1") (pintype "passive"))
      (node (ref "R1") (pin "1") (pinfunction "1_1") (pintype "passive"))
      (node (ref "R2") (pin "2") (pinfunction "2_2") (pintype "passive"))
      (node (ref "RN3") (pin "1") (pinfunction "1_1") (pintype "passive"))
      (node (ref "RN3") (pin "2") (pinfunction "1_2") (pintype "passive"))
      (node (ref "RN3") (pin "4") (pinfunction "1_4") (pintype "passive"))
      (node (ref "RN4") (pin "5") (pinfunction "2_5") (pintype "passive"))
      (node (ref "RN4") (pin "7") (pinfunction "2_7") (pintype "passive"))
      (node (ref "U1") (pin "14") (pinfunction "VCC_14") (pintype "power_in"))
      (node (ref "U1") (pin "2") (pinfunction "UVCC_2") (pintype "power_in"))
      (node (ref "U1") (pin "34") (pinfunction "VCC1_34") (pintype "power_in"))
    )
    (net (code "74") (name "AGND") (class "Default")
      (node (ref "JP11") (pin "1") (pinfunction "1_1") (pintype "passive"))
      (node (ref "L5") (pin "1") (pinfunction "1_1") (pintype "passive"))
      (node (ref "U2") (pin "37") (pinfunction "AGND1_37") (pintype "bidirectional"))
      (node (ref "U2") (pin "40") (pinfunction "AGND2_40") (pintype "bidirectional"))
      (node (ref "U2") (pin "41") (pinfunction "AGND3_41") (pintype "bidirectional"))
      (node (ref "U2") (pin "47") (pinfunction "AGND4_47") (pintype "bidirectional"))
      (node (ref "X4") (pin "1") (pinfunction "1_1") (pintype "passive"))
    )
    (net (code "75") (name "GND") (class "Default")
      (node (ref "C1") (pin "2") (pinfunction "2_2") (pintype "passive"))
      (node (ref "C11") (pin "1") (pinfunction "1_1") (pintype "passive"))
      (node (ref "C12") (pin "1") (pinfunction "1_1") (pintype "passive"))
      (node (ref "C13") (pin "1") (pinfunction "1_1") (pintype "passive"))
      (node (ref "C14") (pin "2") (pinfunction "2_2") (pintype "passive"))
      (node (ref "C15") (pin "2") (pinfunction "2_2") (pintype "passive"))
      (node (ref "C17") (pin "1") (pinfunction "1_1") (pintype "passive"))
      (node (ref "C18") (pin "2") (pinfunction "2_2") (pintype "passive"))
      (node (ref "C19") (pin "2") (pinfunction "2_2") (pintype "passive"))
      (node (ref "C2") (pin "2") (pinfunction "2_2") (pintype "passive"))
      (node (ref "C20") (pin "1") (pinfunction "1_1") (pintype "passive"))
      (node (ref "C21") (pin "1") (pinfunction "1_1") (pintype "passive"))
      (node (ref "C22") (pin "1") (pinfunction "1_1") (pintype "passive"))
      (node (ref "C23") (pin "2") (pinfunction "2_2") (pintype "passive"))
      (node (ref "C24") (pin "1") (pinfunction "1_1") (pintype "passive"))
      (node (ref "C25") (pin "1") (pinfunction "1_1") (pintype "passive"))
      (node (ref "C26") (pin "1") (pinfunction "1_1") (pintype "passive"))
      (node (ref "C28") (pin "2") (pinfunction "2_2") (pintype "passive"))
      (node (ref "C29") (pin "2") (pinfunction "2_2") (pintype "passive"))
      (node (ref "C3") (pin "2") (pinfunction "2_2") (pintype "passive"))
      (node (ref "C30") (pin "1") (pinfunction "1_1") (pintype "passive"))
      (node (ref "C31") (pin "1") (pinfunction "1_1") (pintype "passive"))
      (node (ref "C32") (pin "1") (pinfunction "1_1") (pintype "passive"))
      (node (ref "C33") (pin "1") (pinfunction "1_1") (pintype "passive"))
      (node (ref "C34") (pin "1") (pinfunction "1_1") (pintype "passive"))
      (node (ref "C35") (pin "1") (pinfunction "1_1") (pintype "passive"))
      (node (ref "C4") (pin "1") (pinfunction "1_1") (pintype "passive"))
      (node (ref "C5") (pin "1") (pinfunction "1_1") (pintype "passive"))
      (node (ref "C7") (pin "2") (pinfunction "2_2") (pintype "passive"))
      (node (ref "C8") (pin "2") (pinfunction "2_2") (pintype "passive"))
      (node (ref "C9") (pin "1") (pinfunction "1_1") (pintype "passive"))
      (node (ref "IC1") (pin "2") (pinfunction "GND_2") (pintype "bidirectional"))
      (node (ref "IC2") (pin "2") (pinfunction "GND_2") (pintype "bidirectional"))
      (node (ref "IC3") (pin "4") (pinfunction "V-_4") (pintype "power_in"))
      (node (ref "IC4") (pin "2") (pinfunction "VSS_2") (pintype "power_in"))
      (node (ref "IC5") (pin "8") (pinfunction "GND_8") (pintype "bidirectional"))
      (node (ref "IC6") (pin "6") (pinfunction "VSS_6") (pintype "bidirectional"))
      (node (ref "IC7") (pin "2") (pinfunction "GND_2") (pintype "input"))
      (node (ref "IC8") (pin "2") (pinfunction "GND_2") (pintype "input"))
      (node (ref "ICSP") (pin "6") (pinfunction "6_6") (pintype "passive"))
      (node (ref "J1") (pin "6") (pinfunction "6_6") (pintype "passive"))
      (node (ref "J1") (pin "7") (pinfunction "7_7") (pintype "passive"))
      (node (ref "JP1") (pin "1") (pinfunction "1_1") (pintype "passive"))
      (node (ref "JP13") (pin "13") (pinfunction "13_13") (pintype "passive"))
      (node (ref "JP3") (pin "7") (pinfunction "7_7") (pintype "passive"))
      (node (ref "L") (pin "C") (pinfunction "C_C") (pintype "passive"))
      (node (ref "L2") (pin "1") (pinfunction "1_1") (pintype "passive"))
      (node (ref "L5") (pin "2") (pinfunction "2_2") (pintype "passive"))
      (node (ref "ON") (pin "C") (pinfunction "C_C") (pintype "passive"))
      (node (ref "R10") (pin "2") (pinfunction "2_2") (pintype "passive"))
      (node (ref "R11") (pin "2") (pinfunction "2_2") (pintype "passive"))
      (node (ref "R13") (pin "2") (pinfunction "2_2") (pintype "passive"))
      (node (ref "R15") (pin "2") (pinfunction "2_2") (pintype "passive"))
      (node (ref "R3") (pin "2") (pinfunction "2_2") (pintype "passive"))
      (node (ref "R6") (pin "2") (pinfunction "2_2") (pintype "passive"))
      (node (ref "R8") (pin "2") (pinfunction "2_2") (pintype "passive"))
      (node (ref "R9") (pin "2") (pinfunction "2_2") (pintype "passive"))
      (node (ref "RN5") (pin "3") (pinfunction "1_3") (pintype "passive"))
      (node (ref "RN6") (pin "5") (pinfunction "2_5") (pintype "passive"))
      (node (ref "RN6") (pin "6") (pinfunction "2_6") (pintype "passive"))
      (node (ref "RN6") (pin "7") (pinfunction "2_7") (pintype "passive"))
      (node (ref "RN6") (pin "8") (pinfunction "2_8") (pintype "passive"))
      (node (ref "S1") (pin "1") (pinfunction "1_1") (pintype "passive"))
      (node (ref "S1") (pin "2") (pinfunction "2_2") (pintype "passive"))
      (node (ref "S2") (pin "4") (pinfunction "4_4") (pintype "passive"))
      (node (ref "U$6") (pin "P$1") (pinfunction "GND_P$1") (pintype "bidirectional"))
      (node (ref "U1") (pin "15") (pinfunction "GND_15") (pintype "power_in"))
      (node (ref "U1") (pin "23") (pinfunction "GND1_23") (pintype "power_in"))
      (node (ref "U1") (pin "33") (pinfunction "(#HWB)PE2_33") (pintype "bidirectional"))
      (node (ref "U1") (pin "35") (pinfunction "GND2_35") (pintype "power_in"))
      (node (ref "U1") (pin "43") (pinfunction "GND3_43") (pintype "power_in"))
      (node (ref "U1") (pin "EXP") (pinfunction "PAD_EXP") (pintype "power_in"))
      (node (ref "U2") (pin "16") (pinfunction "DGND2_16") (pintype "bidirectional"))
      (node (ref "U2") (pin "20") (pinfunction "DGND3_20") (pintype "bidirectional"))
      (node (ref "U2") (pin "21") (pinfunction "DGND4_21") (pintype "bidirectional"))
      (node (ref "U2") (pin "22") (pinfunction "DGND5_22") (pintype "bidirectional"))
      (node (ref "U2") (pin "35") (pinfunction "DGND6_35") (pintype "bidirectional"))
      (node (ref "U2") (pin "4") (pinfunction "DGND1_4") (pintype "bidirectional"))
      (node (ref "X1") (pin "S1") (pinfunction "SH1_S1") (pintype "passive"))
      (node (ref "X1") (pin "S2") (pinfunction "SH2_S2") (pintype "passive"))
      (node (ref "X1") (pin "S3") (pinfunction "SH3_S3") (pintype "passive"))
      (node (ref "X1") (pin "S4") (pinfunction "SH4_S4") (pintype "passive"))
      (node (ref "X1") (pin "S5") (pinfunction "SH5_S5") (pintype "passive"))
      (node (ref "X1") (pin "S6") (pinfunction "SH6_S6") (pintype "passive"))
      (node (ref "X2") (pin "1") (pinfunction "1_1") (pintype "passive"))
      (node (ref "X3") (pin "6") (pinfunction "GND_6") (pintype "bidirectional"))
      (node (ref "X3") (pin "S1") (pinfunction "GND1_S1") (pintype "bidirectional"))
      (node (ref "X3") (pin "S2") (pinfunction "GND3_S2") (pintype "bidirectional"))
    )
    (net (code "76") (name "Net-(C25-Pad2)") (class "Default")
      (node (ref "C25") (pin "2") (pinfunction "2_2") (pintype "passive"))
      (node (ref "R17") (pin "2") (pinfunction "2_2") (pintype "passive"))
    )
    (net (code "77") (name "Net-(C26-Pad2)") (class "Default")
      (node (ref "C26") (pin "2") (pinfunction "2_2") (pintype "passive"))
      (node (ref "R18") (pin "2") (pinfunction "2_2") (pintype "passive"))
    )
    (net (code "78") (name "Net-(F2-Pad1)") (class "Default")
      (node (ref "F2") (pin "1") (pinfunction "1_1") (pintype "bidirectional"))
      (node (ref "X2") (pin "2") (pinfunction "2_2") (pintype "passive"))
    )
    (net (code "79") (name "Net-(IC1-EN)") (class "Default")
      (node (ref "IC1") (pin "3") (pinfunction "EN_3") (pintype "bidirectional"))
      (node (ref "S2") (pin "5") (pinfunction "5_5") (pintype "passive"))
    )
    (net (code "80") (name "Net-(IC1-SW)") (class "Default")
      (node (ref "IC1") (pin "1") (pinfunction "SW_1") (pintype "bidirectional"))
      (node (ref "L1") (pin "1") (pinfunction "1_1") (pintype "bidirectional"))
    )
    (net (code "81") (name "Net-(IC1-VFB)") (class "Default")
      (node (ref "IC1") (pin "4") (pinfunction "VFB_4") (pintype "bidirectional"))
      (node (ref "R2") (pin "1") (pinfunction "1_1") (pintype "passive"))
      (node (ref "R3") (pin "1") (pinfunction "1_1") (pintype "passive"))
    )
    (net (code "82") (name "Net-(IC3A--IN)") (class "Default")
      (node (ref "IC3") (pin "1") (pinfunction "OUT_1") (pintype "output"))
      (node (ref "IC3") (pin "2") (pinfunction "-IN_2") (pintype "input"))
    )
    (net (code "83") (name "Net-(IC3B--IN)") (class "Default")
      (node (ref "IC3") (pin "6") (pinfunction "-IN_6") (pintype "input"))
      (node (ref "IC3") (pin "7") (pinfunction "OUT_7") (pintype "output"))
      (node (ref "RN3") (pin "3") (pinfunction "1_3") (pintype "passive"))
    )
    (net (code "84") (name "Net-(IC4-PROG)") (class "Default")
      (node (ref "IC4") (pin "5") (pinfunction "PROG_5") (pintype "input"))
      (node (ref "RN6") (pin "1") (pinfunction "1_1") (pintype "passive"))
      (node (ref "RN6") (pin "2") (pinfunction "1_2") (pintype "passive"))
    )
    (net (code "85") (name "Net-(IC4-STAT)") (class "Default")
      (node (ref "IC4") (pin "1") (pinfunction "STAT_1") (pintype "output"))
      (node (ref "RN2") (pin "7") (pinfunction "2_7") (pintype "passive"))
      (node (ref "RN2") (pin "8") (pinfunction "2_8") (pintype "passive"))
    )
    (net (code "86") (name "Net-(JP10-Pad1)") (class "Default")
      (node (ref "JP10") (pin "1") (pinfunction "1_1") (pintype "passive"))
      (node (ref "R16") (pin "1") (pinfunction "1_1") (pintype "passive"))
    )
    (net (code "87") (name "Net-(JP11-Pad2)") (class "Default")
      (node (ref "JP11") (pin "2") (pinfunction "2_2") (pintype "passive"))
      (node (ref "PC1") (pin "-") (pinfunction "-_-") (pintype "passive"))
      (node (ref "X4") (pin "3") (pinfunction "3_3") (pintype "passive"))
    )
    (net (code "88") (name "Net-(JP11-Pad3)") (class "Default")
      (node (ref "JP11") (pin "3") (pinfunction "3_3") (pintype "passive"))
      (node (ref "PC2") (pin "-") (pinfunction "-_-") (pintype "passive"))
      (node (ref "X4") (pin "2") (pinfunction "2_2") (pintype "passive"))
    )
    (net (code "89") (name "Net-(Q4-2)") (class "Default")
      (node (ref "C18") (pin "1") (pinfunction "1_1") (pintype "passive"))
      (node (ref "Q4") (pin "3") (pinfunction "2_3") (pintype "passive"))
      (node (ref "R7") (pin "1") (pinfunction "1_1") (pintype "passive"))
      (node (ref "U2") (pin "18") (pinfunction "XTAL1/MCLK_18") (pintype "bidirectional"))
    )
    (net (code "90") (name "Net-(RN2B-1)") (class "Default")
      (node (ref "CHG") (pin "C") (pinfunction "C_C") (pintype "passive"))
      (node (ref "RN2") (pin "1") (pinfunction "1_1") (pintype "passive"))
      (node (ref "RN2") (pin "2") (pinfunction "1_2") (pintype "passive"))
    )
    (net (code "91") (name "Net-(RN3A-2)") (class "Default")
      (node (ref "RN3") (pin "8") (pinfunction "2_8") (pintype "passive"))
      (node (ref "RX") (pin "A") (pinfunction "A_A") (pintype "passive"))
    )
    (net (code "92") (name "Net-(RN3B-2)") (class "Default")
      (node (ref "RN3") (pin "7") (pinfunction "2_7") (pintype "passive"))
      (node (ref "TX") (pin "A") (pinfunction "A_A") (pintype "passive"))
    )
    (net (code "93") (name "Net-(RN3C-2)") (class "Default")
      (node (ref "L") (pin "A") (pinfunction "A_A") (pintype "passive"))
      (node (ref "RN3") (pin "6") (pinfunction "2_6") (pintype "passive"))
    )
    (net (code "94") (name "Net-(RN3D-2)") (class "Default")
      (node (ref "ON") (pin "A") (pinfunction "A_A") (pintype "passive"))
      (node (ref "RN3") (pin "5") (pinfunction "2_5") (pintype "passive"))
    )
    (net (code "95") (name "Net-(RN5A-2)") (class "Default")
      (node (ref "JP4") (pin "1") (pinfunction "1_1") (pintype "passive"))
      (node (ref "RN5") (pin "8") (pinfunction "2_8") (pintype "passive"))
    )
    (net (code "96") (name "Net-(RN5B-2)") (class "Default")
      (node (ref "RN5") (pin "6") (pinfunction "2_6") (pintype "passive"))
      (node (ref "RN5") (pin "7") (pinfunction "2_7") (pintype "passive"))
    )
    (net (code "97") (name "Net-(U2-GPIO2{slash}DCLK)") (class "Default")
      (node (ref "R9") (pin "1") (pinfunction "1_1") (pintype "passive"))
      (node (ref "U2") (pin "10") (pinfunction "GPIO3/SDATA_10") (pintype "bidirectional"))
      (node (ref "U2") (pin "11") (pinfunction "GPIO6_11") (pintype "bidirectional"))
      (node (ref "U2") (pin "12") (pinfunction "GPIO7_12") (pintype "bidirectional"))
      (node (ref "U2") (pin "9") (pinfunction "GPIO2/DCLK_9") (pintype "bidirectional"))
    )
    (net (code "98") (name "Net-(U2-GPIO4{slash}I2S_LROUT)") (class "Default")
      (node (ref "R11") (pin "1") (pinfunction "1_1") (pintype "passive"))
      (node (ref "U2") (pin "36") (pinfunction "GPIO4/I2S_LROUT_36") (pintype "bidirectional"))
    )
    (net (code "99") (name "Net-(U2-GPIO5{slash}I2C_MCLK)") (class "Default")
      (node (ref "R10") (pin "1") (pinfunction "1_1") (pintype "passive"))
      (node (ref "U2") (pin "25") (pinfunction "GPIO5/I2C_MCLK_25") (pintype "bidirectional"))
    )
    (net (code "100") (name "Net-(U2-RCAP)") (class "Default")
      (node (ref "C23") (pin "1") (pinfunction "1_1") (pintype "passive"))
      (node (ref "U2") (pin "44") (pinfunction "RCAP_44") (pintype "bidirectional"))
    )
    (net (code "101") (name "Net-(U2-XTAL2)") (class "Default")
      (node (ref "C19") (pin "1") (pinfunction "1_1") (pintype "passive"))
      (node (ref "Q4") (pin "1") (pinfunction "1_1") (pintype "passive"))
      (node (ref "R7") (pin "2") (pinfunction "2_2") (pintype "passive"))
      (node (ref "U2") (pin "17") (pinfunction "XTAL2_17") (pintype "bidirectional"))
    )
    (net (code "102") (name "UGND") (class "Default")
      (node (ref "C10") (pin "1") (pinfunction "1_1") (pintype "passive"))
      (node (ref "L2") (pin "2") (pinfunction "2_2") (pintype "passive"))
      (node (ref "U1") (pin "5") (pinfunction "UGND_5") (pintype "power_in"))
      (node (ref "X1") (pin "P5") (pinfunction "GND_P5") (pintype "passive"))
    )
    (net (code "103") (name "VIN") (class "Default")
      (node (ref "C1") (pin "1") (pinfunction "1_1") (pintype "passive"))
      (node (ref "C2") (pin "1") (pinfunction "1_1") (pintype "passive"))
      (node (ref "D2") (pin "C") (pinfunction "C_C") (pintype "passive"))
      (node (ref "IC1") (pin "6") (pinfunction "VIN_6") (pintype "bidirectional"))
      (node (ref "L1") (pin "2") (pinfunction "2_2") (pintype "bidirectional"))
      (node (ref "S2") (pin "6") (pinfunction "6_6") (pintype "passive"))
      (node (ref "T1") (pin "2") (pinfunction "S_2") (pintype "passive"))
    )
    (net (code "104") (name "VUSB") (class "Default")
      (node (ref "C17") (pin "2") (pinfunction "2_2") (pintype "passive"))
      (node (ref "C3") (pin "1") (pinfunction "1_1") (pintype "passive"))
      (node (ref "C4") (pin "2") (pinfunction "2_2") (pintype "passive"))
      (node (ref "CHG") (pin "A") (pinfunction "A_A") (pintype "passive"))
      (node (ref "D2") (pin "A") (pinfunction "A_A") (pintype "passive"))
      (node (ref "F1") (pin "2") (pinfunction "2_2") (pintype "bidirectional"))
      (node (ref "IC4") (pin "4") (pinfunction "VIN_4") (pintype "power_in"))
      (node (ref "JP1") (pin "2") (pinfunction "2_2") (pintype "passive"))
      (node (ref "RN6") (pin "4") (pinfunction "1_4") (pintype "passive"))
      (node (ref "T1") (pin "3") (pinfunction "G_3") (pintype "passive"))
      (node (ref "U1") (pin "7") (pinfunction "VBUS_7") (pintype "input"))
    )
    (net (code "105") (name "V_BATT") (class "Default")
      (node (ref "F2") (pin "2") (pinfunction "2_2") (pintype "bidirectional"))
      (node (ref "IC4") (pin "3") (pinfunction "VBAT_3") (pintype "power_in"))
      (node (ref "T1") (pin "1") (pinfunction "D_1") (pintype "passive"))
    )
    (net (code "106") (name "unconnected-(IC7-BP-Pad4)") (class "Default")
      (node (ref "IC7") (pin "4") (pinfunction "BP_4") (pintype "input"))
    )
    (net (code "107") (name "unconnected-(IC8-BP-Pad4)") (class "Default")
      (node (ref "IC8") (pin "4") (pinfunction "BP_4") (pintype "input"))
    )
    (net (code "108") (name "unconnected-(J1-Pad1)") (class "Default")
      (node (ref "J1") (pin "1") (pinfunction "1_1") (pintype "passive"))
    )
    (net (code "109") (name "unconnected-(ORIGIN-TESTP-PadX)") (class "Default")
      (node (ref "ORIGIN") (pin "X") (pinfunction "TESTP_X") (pintype "passive"))
    )
    (net (code "110") (name "unconnected-(RN2C-1-Pad3)") (class "Default")
      (node (ref "RN2") (pin "3") (pinfunction "1_3") (pintype "passive"))
    )
    (net (code "111") (name "unconnected-(RN2C-2-Pad6)") (class "Default")
      (node (ref "RN2") (pin "6") (pinfunction "2_6") (pintype "passive"))
    )
    (net (code "112") (name "unconnected-(RN2D-1-Pad4)") (class "Default")
      (node (ref "RN2") (pin "4") (pinfunction "1_4") (pintype "passive"))
    )
    (net (code "113") (name "unconnected-(RN2D-2-Pad5)") (class "Default")
      (node (ref "RN2") (pin "5") (pinfunction "2_5") (pintype "passive"))
    )
    (net (code "114") (name "unconnected-(RN5D-1-Pad4)") (class "Default")
      (node (ref "RN5") (pin "4") (pinfunction "1_4") (pintype "passive"))
    )
    (net (code "115") (name "unconnected-(RN5D-2-Pad5)") (class "Default")
      (node (ref "RN5") (pin "5") (pinfunction "2_5") (pintype "passive"))
    )
    (net (code "116") (name "unconnected-(RN6C-1-Pad3)") (class "Default")
      (node (ref "RN6") (pin "3") (pinfunction "1_3") (pintype "passive"))
    )
    (net (code "117") (name "unconnected-(U2-GBUF-Pad42)") (class "Default")
      (node (ref "U2") (pin "42") (pinfunction "GBUF_42") (pintype "bidirectional"))
    )
    (net (code "118") (name "unconnected-(U2-LINEIN-Pad48)") (class "Default")
      (node (ref "U2") (pin "48") (pinfunction "LINEIN_48") (pintype "bidirectional"))
    )
    (net (code "119") (name "unconnected-(U2-MICN-Pad2)") (class "Default")
      (node (ref "U2") (pin "2") (pinfunction "MICN_2") (pintype "bidirectional"))
    )
    (net (code "120") (name "unconnected-(U2-MICP-Pad1)") (class "Default")
      (node (ref "U2") (pin "1") (pinfunction "MICP_1") (pintype "bidirectional"))
    )
    (net (code "121") (name "unconnected-(U2-TX-Pad27)") (class "Default")
      (node (ref "U2") (pin "27") (pinfunction "TX_27") (pintype "bidirectional"))
    )
    (net (code "122") (name "unconnected-(U2-VCO-Pad15)") (class "Default")
      (node (ref "U2") (pin "15") (pinfunction "VCO_15") (pintype "bidirectional"))
    )
    (net (code "123") (name "unconnected-(X3-NC-Pad1)") (class "Default")
      (node (ref "X3") (pin "1") (pinfunction "NC_1") (pintype "bidirectional"))
    )
    (net (code "124") (name "unconnected-(X3-PadCD1)") (class "Default")
      (node (ref "X3") (pin "CD1") (pinfunction "CD1_CD1") (pintype "bidirectional"))
    )
    (net (code "125") (name "unconnected-(X3-PadCD2)") (class "Default")
      (node (ref "X3") (pin "CD2") (pinfunction "CD2_CD2") (pintype "bidirectional"))
    )
    (net (code "126") (name "unconnected-(X3-RSV-Pad8)") (class "Default")
      (node (ref "X3") (pin "8") (pinfunction "RSV_8") (pintype "bidirectional"))
    )
  )
)
